# MultiRotorHub.net
KiCad netlist of a schematic drawn in EAGLE
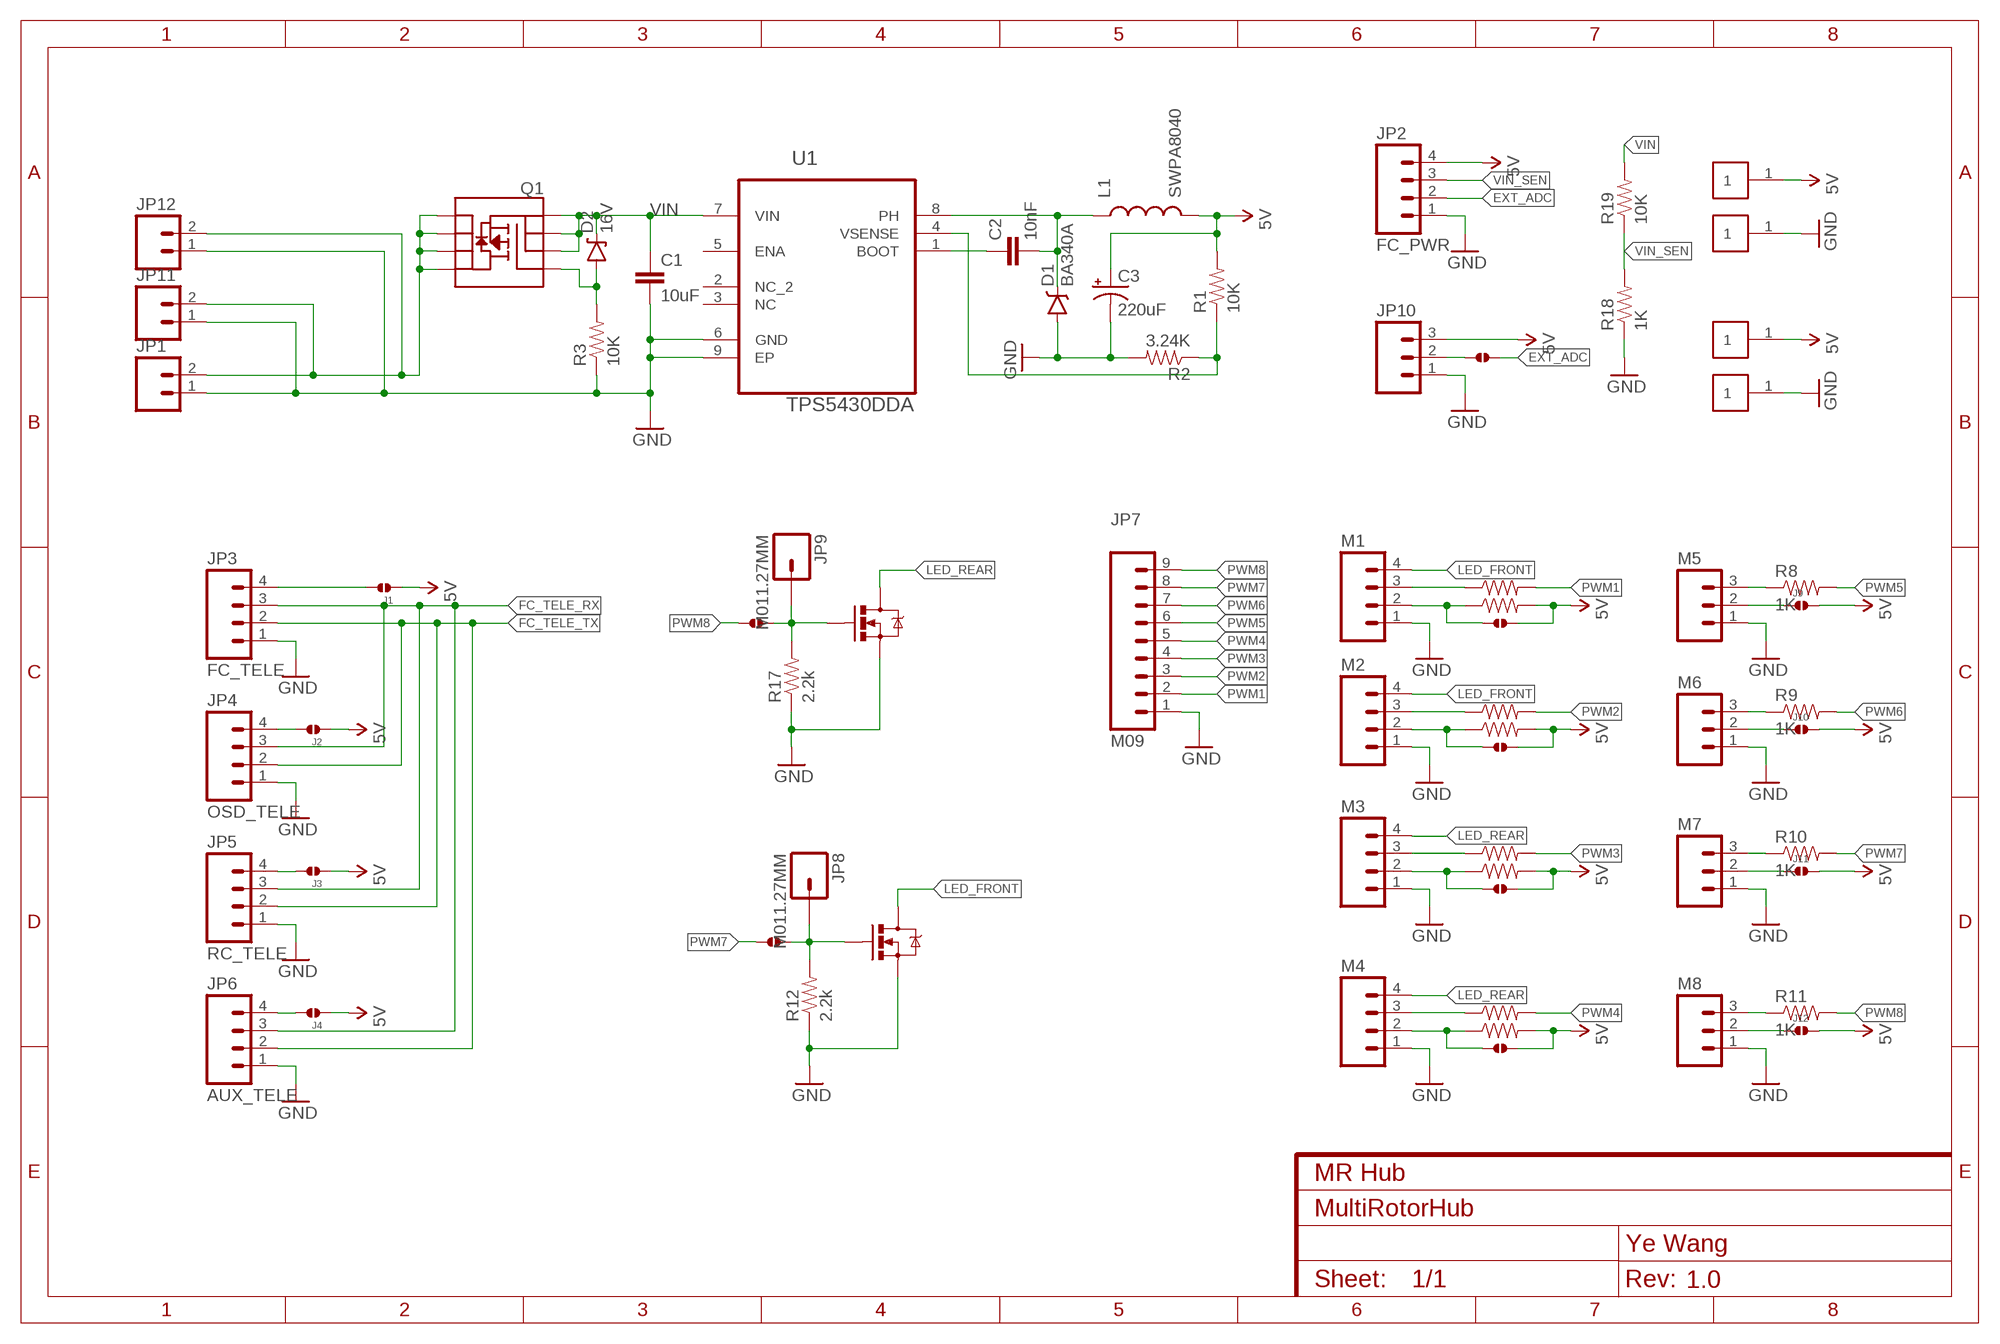
[diagram p0: schematic, sheet 1]

(export (version "E")
  (design (tool "Eeschema 10.0.6"))
  (components
    (comp (ref "C1")
      (value "10uF")
      (footprint "eagle-import:1206")
      (libsource (lib "eagle-import") (part "CAP1206"))
    )
    (comp (ref "C2")
      (value "10nF")
      (footprint "eagle-import:0603-CAP")
      (libsource (lib "eagle-import") (part "10NF/10000PF-50V-10%(0603)"))
    )
    (comp (ref "C3")
      (value "220uF")
      (footprint "eagle-import:PANASONIC_D")
      (libsource (lib "eagle-import") (part "CAP_POLD"))
    )
    (comp (ref "CON1")
      (value "CON1P2.54MM")
      (footprint "eagle-import:SMD2.54MM")
      (libsource (lib "eagle-import") (part "CON1P2.54MM"))
    )
    (comp (ref "CON2")
      (value "CON1P2.54MM")
      (footprint "eagle-import:SMD2.54MM")
      (libsource (lib "eagle-import") (part "CON1P2.54MM"))
    )
    (comp (ref "CON3")
      (value "CON1P2.54MM")
      (footprint "eagle-import:SMD2.54MM")
      (libsource (lib "eagle-import") (part "CON1P2.54MM"))
    )
    (comp (ref "CON4")
      (value "CON1P2.54MM")
      (footprint "eagle-import:SMD2.54MM")
      (libsource (lib "eagle-import") (part "CON1P2.54MM"))
    )
    (comp (ref "D1")
      (value "BA340A")
      (footprint "eagle-import:SMA-DIODE")
      (libsource (lib "eagle-import") (part "B340A"))
    )
    (comp (ref "D2")
      (value "16V")
      (footprint "eagle-import:SOD-123")
      (libsource (lib "eagle-import") (part "DIODE-ZENER16V"))
    )
    (comp (ref "J1")
      (value "SOLDERJUMPER.2.MED")
      (footprint "eagle-import:2.MED")
      (libsource (lib "eagle-import") (part "SOLDERJUMPER.2.MED"))
    )
    (comp (ref "J2")
      (value "SOLDERJUMPER.2.MED")
      (footprint "eagle-import:2.MED")
      (libsource (lib "eagle-import") (part "SOLDERJUMPER.2.MED"))
    )
    (comp (ref "J3")
      (value "SOLDERJUMPER.2.MED")
      (footprint "eagle-import:2.MED")
      (libsource (lib "eagle-import") (part "SOLDERJUMPER.2.MED"))
    )
    (comp (ref "J4")
      (value "SOLDERJUMPER.2.MED")
      (footprint "eagle-import:2.MED")
      (libsource (lib "eagle-import") (part "SOLDERJUMPER.2.MED"))
    )
    (comp (ref "J5")
      (value "SOLDERJUMPER.2.MED")
      (footprint "eagle-import:2.MED")
      (libsource (lib "eagle-import") (part "SOLDERJUMPER.2.MED"))
    )
    (comp (ref "J6")
      (value "SOLDERJUMPER.2.MED")
      (footprint "eagle-import:2.MED")
      (libsource (lib "eagle-import") (part "SOLDERJUMPER.2.MED"))
    )
    (comp (ref "J7")
      (value "SOLDERJUMPER.2.MED")
      (footprint "eagle-import:2.MED")
      (libsource (lib "eagle-import") (part "SOLDERJUMPER.2.MED"))
    )
    (comp (ref "J8")
      (value "SOLDERJUMPER.2.MED")
      (footprint "eagle-import:2.MED")
      (libsource (lib "eagle-import") (part "SOLDERJUMPER.2.MED"))
    )
    (comp (ref "J9")
      (value "SOLDERJUMPER.2.MED")
      (footprint "eagle-import:2.MED")
      (libsource (lib "eagle-import") (part "SOLDERJUMPER.2.MED"))
    )
    (comp (ref "J10")
      (value "SOLDERJUMPER.2.MED")
      (footprint "eagle-import:2.MED")
      (libsource (lib "eagle-import") (part "SOLDERJUMPER.2.MED"))
    )
    (comp (ref "J11")
      (value "SOLDERJUMPER.2.MED")
      (footprint "eagle-import:2.MED")
      (libsource (lib "eagle-import") (part "SOLDERJUMPER.2.MED"))
    )
    (comp (ref "J12")
      (value "SOLDERJUMPER.2.MED")
      (footprint "eagle-import:2.MED")
      (libsource (lib "eagle-import") (part "SOLDERJUMPER.2.MED"))
    )
    (comp (ref "J13")
      (value "SOLDERJUMPER.2.MED")
      (footprint "eagle-import:2.MED")
      (libsource (lib "eagle-import") (part "SOLDERJUMPER.2.MED"))
    )
    (comp (ref "J14")
      (value "SOLDERJUMPER.2.MED")
      (footprint "eagle-import:2.MED")
      (libsource (lib "eagle-import") (part "SOLDERJUMPER.2.MED"))
    )
    (comp (ref "J15")
      (value "SOLDERJUMPER.2.MED")
      (footprint "eagle-import:2.MED")
      (libsource (lib "eagle-import") (part "SOLDERJUMPER.2.MED"))
    )
    (comp (ref "JP1")
      (value "M02PTH")
      (footprint "eagle-import:1X02")
      (libsource (lib "eagle-import") (part "M02PTH"))
    )
    (comp (ref "JP2")
      (value "FC_PWR")
      (footprint "eagle-import:1X04-1.27MM")
      (libsource (lib "eagle-import") (part "M041.27MM"))
    )
    (comp (ref "JP3")
      (value "FC_TELE")
      (footprint "eagle-import:1X04-1.27MM")
      (libsource (lib "eagle-import") (part "M041.27MM"))
    )
    (comp (ref "JP4")
      (value "OSD_TELE")
      (footprint "eagle-import:1X04-1.27MM")
      (libsource (lib "eagle-import") (part "M041.27MM"))
    )
    (comp (ref "JP5")
      (value "RC_TELE")
      (footprint "eagle-import:1X04-1.27MM")
      (libsource (lib "eagle-import") (part "M041.27MM"))
    )
    (comp (ref "JP6")
      (value "AUX_TELE")
      (footprint "eagle-import:1X04-1.27MM")
      (libsource (lib "eagle-import") (part "M041.27MM"))
    )
    (comp (ref "JP7")
      (value "M09")
      (footprint "eagle-import:1X09")
      (libsource (lib "eagle-import") (part "M09"))
    )
    (comp (ref "JP8")
      (value "M011.27MM")
      (footprint "eagle-import:1X01-1.27MM")
      (libsource (lib "eagle-import") (part "M011.27MM"))
    )
    (comp (ref "JP9")
      (value "M011.27MM")
      (footprint "eagle-import:1X01-1.27MM")
      (libsource (lib "eagle-import") (part "M011.27MM"))
    )
    (comp (ref "JP10")
      (value "M03M03-1.27MM")
      (footprint "eagle-import:1X03-1.27MM")
      (libsource (lib "eagle-import") (part "M03M03-1.27MM"))
    )
    (comp (ref "JP11")
      (value "M02PTH")
      (footprint "eagle-import:1X02")
      (libsource (lib "eagle-import") (part "M02PTH"))
    )
    (comp (ref "JP12")
      (value "M02PTH")
      (footprint "eagle-import:1X02")
      (libsource (lib "eagle-import") (part "M02PTH"))
    )
    (comp (ref "L1")
      (value "SWPA8040")
      (footprint "eagle-import:INC8040")
      (libsource (lib "eagle-import") (part "SWPA8040"))
    )
    (comp (ref "M1")
      (value "M04PTH")
      (footprint "eagle-import:1X04")
      (libsource (lib "eagle-import") (part "M04PTH"))
    )
    (comp (ref "M2")
      (value "M04PTH")
      (footprint "eagle-import:1X04")
      (libsource (lib "eagle-import") (part "M04PTH"))
    )
    (comp (ref "M3")
      (value "M04PTH")
      (footprint "eagle-import:1X04")
      (libsource (lib "eagle-import") (part "M04PTH"))
    )
    (comp (ref "M4")
      (value "M04PTH")
      (footprint "eagle-import:1X04")
      (libsource (lib "eagle-import") (part "M04PTH"))
    )
    (comp (ref "M5")
      (value "M03PTH")
      (footprint "eagle-import:1X03")
      (libsource (lib "eagle-import") (part "M03PTH"))
    )
    (comp (ref "M6")
      (value "M03PTH")
      (footprint "eagle-import:1X03")
      (libsource (lib "eagle-import") (part "M03PTH"))
    )
    (comp (ref "M7")
      (value "M03PTH")
      (footprint "eagle-import:1X03")
      (libsource (lib "eagle-import") (part "M03PTH"))
    )
    (comp (ref "M8")
      (value "M03PTH")
      (footprint "eagle-import:1X03")
      (libsource (lib "eagle-import") (part "M03PTH"))
    )
    (comp (ref "Q1")
      (value "MOSFET-PCHANNEL-SOIC8SOIC8")
      (footprint "eagle-import:SO08")
      (libsource (lib "eagle-import") (part "MOSFET-PCHANNEL-SOIC8SOIC8"))
    )
    (comp (ref "Q2")
      (value "MOSFET-NCHANNELBSS123LT1G")
      (footprint "eagle-import:SOT23-3")
      (libsource (lib "eagle-import") (part "MOSFET-NCHANNELBSS123LT1G"))
    )
    (comp (ref "Q3")
      (value "MOSFET-NCHANNELBSS123LT1G")
      (footprint "eagle-import:SOT23-3")
      (libsource (lib "eagle-import") (part "MOSFET-NCHANNELBSS123LT1G"))
    )
    (comp (ref "R1")
      (value "10K")
      (footprint "eagle-import:0603-RES")
      (libsource (lib "eagle-import") (part "10KOHM-1/10W-1%(0603)0603"))
    )
    (comp (ref "R2")
      (value "3.24K")
      (footprint "eagle-import:0603-RES")
      (libsource (lib "eagle-import") (part "RESISTOR0603-RES"))
    )
    (comp (ref "R3")
      (value "10K")
      (footprint "eagle-import:0603-RES")
      (libsource (lib "eagle-import") (part "10KOHM-1/10W-1%(0603)0603"))
    )
    (comp (ref "R4")
      (value "1K")
      (footprint "eagle-import:0603-RES")
      (libsource (lib "eagle-import") (part "RESISTOR0603-RES"))
    )
    (comp (ref "R5")
      (value "1K")
      (footprint "eagle-import:0603-RES")
      (libsource (lib "eagle-import") (part "RESISTOR0603-RES"))
    )
    (comp (ref "R6")
      (value "1K")
      (footprint "eagle-import:0603-RES")
      (libsource (lib "eagle-import") (part "RESISTOR0603-RES"))
    )
    (comp (ref "R7")
      (value "1K")
      (footprint "eagle-import:0603-RES")
      (libsource (lib "eagle-import") (part "RESISTOR0603-RES"))
    )
    (comp (ref "R8")
      (value "1K")
      (footprint "eagle-import:0603-RES")
      (libsource (lib "eagle-import") (part "RESISTOR0603-RES"))
    )
    (comp (ref "R9")
      (value "1K")
      (footprint "eagle-import:0603-RES")
      (libsource (lib "eagle-import") (part "RESISTOR0603-RES"))
    )
    (comp (ref "R10")
      (value "1K")
      (footprint "eagle-import:0603-RES")
      (libsource (lib "eagle-import") (part "RESISTOR0603-RES"))
    )
    (comp (ref "R11")
      (value "1K")
      (footprint "eagle-import:0603-RES")
      (libsource (lib "eagle-import") (part "RESISTOR0603-RES"))
    )
    (comp (ref "R12")
      (value "2.2k")
      (footprint "eagle-import:0603-RES")
      (libsource (lib "eagle-import") (part "2.2KOHM-1/10W-1%(0603)"))
    )
    (comp (ref "R13")
      (value "10")
      (footprint "eagle-import:R2512")
      (libsource (lib "eagle-import") (part "RESISTOR2512"))
    )
    (comp (ref "R14")
      (value "10")
      (footprint "eagle-import:R2512")
      (libsource (lib "eagle-import") (part "RESISTOR2512"))
    )
    (comp (ref "R15")
      (value "10")
      (footprint "eagle-import:R2512")
      (libsource (lib "eagle-import") (part "RESISTOR2512"))
    )
    (comp (ref "R16")
      (value "10")
      (footprint "eagle-import:R2512")
      (libsource (lib "eagle-import") (part "RESISTOR2512"))
    )
    (comp (ref "R17")
      (value "2.2k")
      (footprint "eagle-import:0603-RES")
      (libsource (lib "eagle-import") (part "2.2KOHM-1/10W-1%(0603)"))
    )
    (comp (ref "R18")
      (value "1K")
      (footprint "eagle-import:0603-RES")
      (libsource (lib "eagle-import") (part "1KOHM-1/10W-1%(0603)"))
    )
    (comp (ref "R19")
      (value "10K")
      (footprint "eagle-import:0603-RES")
      (libsource (lib "eagle-import") (part "10KOHM-1/10W-1%(0603)0603"))
    )
    (comp (ref "U1")
      (value "TPS5430DDA")
      (footprint "eagle-import:SOIC127P600X170-9N")
      (libsource (lib "eagle-import") (part "TPS5430DDA"))
    )
  )
  (nets
    (net (code "1") (name "5V") (class "Default")
      (node (ref "C3") (pin "+") (pinfunction "+_+") (pintype "passive"))
      (node (ref "CON1") (pin "1") (pinfunction "1_1") (pintype "bidirectional"))
      (node (ref "CON3") (pin "1") (pinfunction "1_1") (pintype "bidirectional"))
      (node (ref "J1") (pin "1") (pinfunction "1_1") (pintype "bidirectional"))
      (node (ref "J10") (pin "2") (pinfunction "2_2") (pintype "bidirectional"))
      (node (ref "J11") (pin "2") (pinfunction "2_2") (pintype "bidirectional"))
      (node (ref "J12") (pin "2") (pinfunction "2_2") (pintype "bidirectional"))
      (node (ref "J2") (pin "1") (pinfunction "1_1") (pintype "bidirectional"))
      (node (ref "J3") (pin "1") (pinfunction "1_1") (pintype "bidirectional"))
      (node (ref "J4") (pin "1") (pinfunction "1_1") (pintype "bidirectional"))
      (node (ref "J5") (pin "2") (pinfunction "2_2") (pintype "bidirectional"))
      (node (ref "J6") (pin "2") (pinfunction "2_2") (pintype "bidirectional"))
      (node (ref "J7") (pin "2") (pinfunction "2_2") (pintype "bidirectional"))
      (node (ref "J8") (pin "2") (pinfunction "2_2") (pintype "bidirectional"))
      (node (ref "J9") (pin "2") (pinfunction "2_2") (pintype "bidirectional"))
      (node (ref "JP10") (pin "3") (pinfunction "3_3") (pintype "passive"))
      (node (ref "JP2") (pin "4") (pinfunction "4_4") (pintype "passive"))
      (node (ref "L1") (pin "2") (pinfunction "2_2") (pintype "passive"))
      (node (ref "R1") (pin "2") (pinfunction "2_2") (pintype "passive"))
      (node (ref "R13") (pin "2") (pinfunction "2_2") (pintype "passive"))
      (node (ref "R14") (pin "2") (pinfunction "2_2") (pintype "passive"))
      (node (ref "R15") (pin "2") (pinfunction "2_2") (pintype "passive"))
      (node (ref "R16") (pin "2") (pinfunction "2_2") (pintype "passive"))
    )
    (net (code "2") (name "EXT_ADC") (class "Default")
      (node (ref "J15") (pin "2") (pinfunction "2_2") (pintype "bidirectional"))
      (node (ref "JP2") (pin "2") (pinfunction "2_2") (pintype "passive"))
    )
    (net (code "3") (name "FC_TELE_RX") (class "Default")
      (node (ref "JP3") (pin "3") (pinfunction "3_3") (pintype "passive"))
      (node (ref "JP4") (pin "3") (pinfunction "3_3") (pintype "passive"))
      (node (ref "JP5") (pin "3") (pinfunction "3_3") (pintype "passive"))
      (node (ref "JP6") (pin "3") (pinfunction "3_3") (pintype "passive"))
    )
    (net (code "4") (name "FC_TELE_TX") (class "Default")
      (node (ref "JP3") (pin "2") (pinfunction "2_2") (pintype "passive"))
      (node (ref "JP4") (pin "2") (pinfunction "2_2") (pintype "passive"))
      (node (ref "JP5") (pin "2") (pinfunction "2_2") (pintype "passive"))
      (node (ref "JP6") (pin "2") (pinfunction "2_2") (pintype "passive"))
    )
    (net (code "5") (name "GND") (class "Default")
      (node (ref "C1") (pin "2") (pinfunction "2_2") (pintype "passive"))
      (node (ref "C3") (pin "-") (pinfunction "-_-") (pintype "passive"))
      (node (ref "CON2") (pin "1") (pinfunction "1_1") (pintype "bidirectional"))
      (node (ref "CON4") (pin "1") (pinfunction "1_1") (pintype "bidirectional"))
      (node (ref "D1") (pin "A") (pinfunction "A_A") (pintype "passive"))
      (node (ref "JP1") (pin "1") (pinfunction "1_1") (pintype "passive"))
      (node (ref "JP10") (pin "1") (pinfunction "1_1") (pintype "passive"))
      (node (ref "JP11") (pin "1") (pinfunction "1_1") (pintype "passive"))
      (node (ref "JP12") (pin "1") (pinfunction "1_1") (pintype "passive"))
      (node (ref "JP2") (pin "1") (pinfunction "1_1") (pintype "passive"))
      (node (ref "JP3") (pin "1") (pinfunction "1_1") (pintype "passive"))
      (node (ref "JP4") (pin "1") (pinfunction "1_1") (pintype "passive"))
      (node (ref "JP5") (pin "1") (pinfunction "1_1") (pintype "passive"))
      (node (ref "JP6") (pin "1") (pinfunction "1_1") (pintype "passive"))
      (node (ref "JP7") (pin "1") (pinfunction "1_1") (pintype "passive"))
      (node (ref "M1") (pin "1") (pinfunction "1_1") (pintype "passive"))
      (node (ref "M2") (pin "1") (pinfunction "1_1") (pintype "passive"))
      (node (ref "M3") (pin "1") (pinfunction "1_1") (pintype "passive"))
      (node (ref "M4") (pin "1") (pinfunction "1_1") (pintype "passive"))
      (node (ref "M5") (pin "1") (pinfunction "1_1") (pintype "passive"))
      (node (ref "M6") (pin "1") (pinfunction "1_1") (pintype "passive"))
      (node (ref "M7") (pin "1") (pinfunction "1_1") (pintype "passive"))
      (node (ref "M8") (pin "1") (pinfunction "1_1") (pintype "passive"))
      (node (ref "Q2") (pin "2") (pinfunction "S_2") (pintype "passive"))
      (node (ref "Q3") (pin "2") (pinfunction "S_2") (pintype "passive"))
      (node (ref "R12") (pin "1") (pinfunction "1_1") (pintype "passive"))
      (node (ref "R17") (pin "1") (pinfunction "1_1") (pintype "passive"))
      (node (ref "R18") (pin "1") (pinfunction "1_1") (pintype "passive"))
      (node (ref "R2") (pin "2") (pinfunction "2_2") (pintype "passive"))
      (node (ref "R3") (pin "1") (pinfunction "1_1") (pintype "passive"))
      (node (ref "U1") (pin "6") (pinfunction "GND_6") (pintype "passive"))
      (node (ref "U1") (pin "9") (pinfunction "EP_9") (pintype "passive"))
    )
    (net (code "6") (name "LED_FRONT") (class "Default")
      (node (ref "M1") (pin "4") (pinfunction "4_4") (pintype "passive"))
      (node (ref "M2") (pin "4") (pinfunction "4_4") (pintype "passive"))
      (node (ref "Q2") (pin "3") (pinfunction "D_3") (pintype "passive"))
    )
    (net (code "7") (name "LED_REAR") (class "Default")
      (node (ref "M3") (pin "4") (pinfunction "4_4") (pintype "passive"))
      (node (ref "M4") (pin "4") (pinfunction "4_4") (pintype "passive"))
      (node (ref "Q3") (pin "3") (pinfunction "D_3") (pintype "passive"))
    )
    (net (code "8") (name "Net-(J1-Pad2)") (class "Default")
      (node (ref "J1") (pin "2") (pinfunction "2_2") (pintype "bidirectional"))
      (node (ref "JP3") (pin "4") (pinfunction "4_4") (pintype "passive"))
    )
    (net (code "9") (name "Net-(J2-Pad2)") (class "Default")
      (node (ref "J2") (pin "2") (pinfunction "2_2") (pintype "bidirectional"))
      (node (ref "JP4") (pin "4") (pinfunction "4_4") (pintype "passive"))
    )
    (net (code "10") (name "Net-(J3-Pad2)") (class "Default")
      (node (ref "J3") (pin "2") (pinfunction "2_2") (pintype "bidirectional"))
      (node (ref "JP5") (pin "4") (pinfunction "4_4") (pintype "passive"))
    )
    (net (code "11") (name "Net-(J4-Pad2)") (class "Default")
      (node (ref "J4") (pin "2") (pinfunction "2_2") (pintype "bidirectional"))
      (node (ref "JP6") (pin "4") (pinfunction "4_4") (pintype "passive"))
    )
    (net (code "12") (name "Net-(J5-Pad1)") (class "Default")
      (node (ref "J5") (pin "1") (pinfunction "1_1") (pintype "bidirectional"))
      (node (ref "M1") (pin "2") (pinfunction "2_2") (pintype "passive"))
      (node (ref "R13") (pin "1") (pinfunction "1_1") (pintype "passive"))
    )
    (net (code "13") (name "Net-(J6-Pad1)") (class "Default")
      (node (ref "J6") (pin "1") (pinfunction "1_1") (pintype "bidirectional"))
      (node (ref "M2") (pin "2") (pinfunction "2_2") (pintype "passive"))
      (node (ref "R14") (pin "1") (pinfunction "1_1") (pintype "passive"))
    )
    (net (code "14") (name "Net-(J7-Pad1)") (class "Default")
      (node (ref "J7") (pin "1") (pinfunction "1_1") (pintype "bidirectional"))
      (node (ref "M3") (pin "2") (pinfunction "2_2") (pintype "passive"))
      (node (ref "R15") (pin "1") (pinfunction "1_1") (pintype "passive"))
    )
    (net (code "15") (name "Net-(J8-Pad1)") (class "Default")
      (node (ref "J8") (pin "1") (pinfunction "1_1") (pintype "bidirectional"))
      (node (ref "M4") (pin "2") (pinfunction "2_2") (pintype "passive"))
      (node (ref "R16") (pin "1") (pinfunction "1_1") (pintype "passive"))
    )
    (net (code "16") (name "Net-(J9-Pad1)") (class "Default")
      (node (ref "J9") (pin "1") (pinfunction "1_1") (pintype "bidirectional"))
      (node (ref "M5") (pin "2") (pinfunction "2_2") (pintype "passive"))
    )
    (net (code "17") (name "Net-(J10-Pad1)") (class "Default")
      (node (ref "J10") (pin "1") (pinfunction "1_1") (pintype "bidirectional"))
      (node (ref "M6") (pin "2") (pinfunction "2_2") (pintype "passive"))
    )
    (net (code "18") (name "Net-(J11-Pad1)") (class "Default")
      (node (ref "J11") (pin "1") (pinfunction "1_1") (pintype "bidirectional"))
      (node (ref "M7") (pin "2") (pinfunction "2_2") (pintype "passive"))
    )
    (net (code "19") (name "Net-(J12-Pad1)") (class "Default")
      (node (ref "J12") (pin "1") (pinfunction "1_1") (pintype "bidirectional"))
      (node (ref "M8") (pin "2") (pinfunction "2_2") (pintype "passive"))
    )
    (net (code "20") (name "Net-(J15-Pad1)") (class "Default")
      (node (ref "J15") (pin "1") (pinfunction "1_1") (pintype "bidirectional"))
      (node (ref "JP10") (pin "2") (pinfunction "2_2") (pintype "passive"))
    )
    (net (code "21") (name "Net-(JP1-Pad2)") (class "Default")
      (node (ref "JP1") (pin "2") (pinfunction "2_2") (pintype "passive"))
      (node (ref "JP11") (pin "2") (pinfunction "2_2") (pintype "passive"))
      (node (ref "JP12") (pin "2") (pinfunction "2_2") (pintype "passive"))
      (node (ref "Q1") (pin "5") (pinfunction "D_5") (pintype "bidirectional"))
      (node (ref "Q1") (pin "6") (pinfunction "D_6") (pintype "bidirectional"))
      (node (ref "Q1") (pin "7") (pinfunction "D_7") (pintype "bidirectional"))
      (node (ref "Q1") (pin "8") (pinfunction "D_8") (pintype "bidirectional"))
    )
    (net (code "22") (name "Net-(M1-Pad3)") (class "Default")
      (node (ref "M1") (pin "3") (pinfunction "3_3") (pintype "passive"))
      (node (ref "R4") (pin "1") (pinfunction "1_1") (pintype "passive"))
    )
    (net (code "23") (name "Net-(M2-Pad3)") (class "Default")
      (node (ref "M2") (pin "3") (pinfunction "3_3") (pintype "passive"))
      (node (ref "R5") (pin "1") (pinfunction "1_1") (pintype "passive"))
    )
    (net (code "24") (name "Net-(M3-Pad3)") (class "Default")
      (node (ref "M3") (pin "3") (pinfunction "3_3") (pintype "passive"))
      (node (ref "R6") (pin "1") (pinfunction "1_1") (pintype "passive"))
    )
    (net (code "25") (name "Net-(M4-Pad3)") (class "Default")
      (node (ref "M4") (pin "3") (pinfunction "3_3") (pintype "passive"))
      (node (ref "R7") (pin "1") (pinfunction "1_1") (pintype "passive"))
    )
    (net (code "26") (name "Net-(M5-Pad3)") (class "Default")
      (node (ref "M5") (pin "3") (pinfunction "3_3") (pintype "passive"))
      (node (ref "R8") (pin "1") (pinfunction "1_1") (pintype "passive"))
    )
    (net (code "27") (name "Net-(M6-Pad3)") (class "Default")
      (node (ref "M6") (pin "3") (pinfunction "3_3") (pintype "passive"))
      (node (ref "R9") (pin "1") (pinfunction "1_1") (pintype "passive"))
    )
    (net (code "28") (name "Net-(M7-Pad3)") (class "Default")
      (node (ref "M7") (pin "3") (pinfunction "3_3") (pintype "passive"))
      (node (ref "R10") (pin "1") (pinfunction "1_1") (pintype "passive"))
    )
    (net (code "29") (name "Net-(M8-Pad3)") (class "Default")
      (node (ref "M8") (pin "3") (pinfunction "3_3") (pintype "passive"))
      (node (ref "R11") (pin "1") (pinfunction "1_1") (pintype "passive"))
    )
    (net (code "30") (name "Net-(Q1-G)") (class "Default")
      (node (ref "D2") (pin "A") (pinfunction "A_A") (pintype "passive"))
      (node (ref "Q1") (pin "4") (pinfunction "G_4") (pintype "bidirectional"))
      (node (ref "R3") (pin "2") (pinfunction "2_2") (pintype "passive"))
    )
    (net (code "31") (name "Net-(Q2-G)") (class "Default")
      (node (ref "J13") (pin "2") (pinfunction "2_2") (pintype "bidirectional"))
      (node (ref "JP8") (pin "1") (pinfunction "1_1") (pintype "passive"))
      (node (ref "Q2") (pin "1") (pinfunction "G_1") (pintype "passive"))
      (node (ref "R12") (pin "2") (pinfunction "2_2") (pintype "passive"))
    )
    (net (code "32") (name "Net-(Q3-G)") (class "Default")
      (node (ref "J14") (pin "2") (pinfunction "2_2") (pintype "bidirectional"))
      (node (ref "JP9") (pin "1") (pinfunction "1_1") (pintype "passive"))
      (node (ref "Q3") (pin "1") (pinfunction "G_1") (pintype "passive"))
      (node (ref "R17") (pin "2") (pinfunction "2_2") (pintype "passive"))
    )
    (net (code "33") (name "Net-(U1-BOOT)") (class "Default")
      (node (ref "C2") (pin "1") (pinfunction "1_1") (pintype "passive"))
      (node (ref "U1") (pin "1") (pinfunction "BOOT_1") (pintype "passive"))
    )
    (net (code "34") (name "Net-(U1-PH)") (class "Default")
      (node (ref "C2") (pin "2") (pinfunction "2_2") (pintype "passive"))
      (node (ref "D1") (pin "C") (pinfunction "C_C") (pintype "passive"))
      (node (ref "L1") (pin "1") (pinfunction "1_1") (pintype "passive"))
      (node (ref "U1") (pin "8") (pinfunction "PH_8") (pintype "output"))
    )
    (net (code "35") (name "Net-(U1-VSENSE)") (class "Default")
      (node (ref "R1") (pin "1") (pinfunction "1_1") (pintype "passive"))
      (node (ref "R2") (pin "1") (pinfunction "1_1") (pintype "passive"))
      (node (ref "U1") (pin "4") (pinfunction "VSENSE_4") (pintype "output"))
    )
    (net (code "36") (name "PWM1") (class "Default")
      (node (ref "JP7") (pin "2") (pinfunction "2_2") (pintype "passive"))
      (node (ref "R4") (pin "2") (pinfunction "2_2") (pintype "passive"))
    )
    (net (code "37") (name "PWM2") (class "Default")
      (node (ref "JP7") (pin "3") (pinfunction "3_3") (pintype "passive"))
      (node (ref "R5") (pin "2") (pinfunction "2_2") (pintype "passive"))
    )
    (net (code "38") (name "PWM3") (class "Default")
      (node (ref "JP7") (pin "4") (pinfunction "4_4") (pintype "passive"))
      (node (ref "R6") (pin "2") (pinfunction "2_2") (pintype "passive"))
    )
    (net (code "39") (name "PWM4") (class "Default")
      (node (ref "JP7") (pin "5") (pinfunction "5_5") (pintype "passive"))
      (node (ref "R7") (pin "2") (pinfunction "2_2") (pintype "passive"))
    )
    (net (code "40") (name "PWM5") (class "Default")
      (node (ref "JP7") (pin "6") (pinfunction "6_6") (pintype "passive"))
      (node (ref "R8") (pin "2") (pinfunction "2_2") (pintype "passive"))
    )
    (net (code "41") (name "PWM6") (class "Default")
      (node (ref "JP7") (pin "7") (pinfunction "7_7") (pintype "passive"))
      (node (ref "R9") (pin "2") (pinfunction "2_2") (pintype "passive"))
    )
    (net (code "42") (name "PWM7") (class "Default")
      (node (ref "J13") (pin "1") (pinfunction "1_1") (pintype "bidirectional"))
      (node (ref "JP7") (pin "8") (pinfunction "8_8") (pintype "passive"))
      (node (ref "R10") (pin "2") (pinfunction "2_2") (pintype "passive"))
    )
    (net (code "43") (name "PWM8") (class "Default")
      (node (ref "J14") (pin "1") (pinfunction "1_1") (pintype "bidirectional"))
      (node (ref "JP7") (pin "9") (pinfunction "9_9") (pintype "passive"))
      (node (ref "R11") (pin "2") (pinfunction "2_2") (pintype "passive"))
    )
    (net (code "44") (name "VIN") (class "Default")
      (node (ref "C1") (pin "1") (pinfunction "1_1") (pintype "passive"))
      (node (ref "D2") (pin "C") (pinfunction "C_C") (pintype "passive"))
      (node (ref "Q1") (pin "1") (pinfunction "S_1") (pintype "bidirectional"))
      (node (ref "Q1") (pin "2") (pinfunction "S_2") (pintype "bidirectional"))
      (node (ref "Q1") (pin "3") (pinfunction "S_3") (pintype "bidirectional"))
      (node (ref "R19") (pin "2") (pinfunction "2_2") (pintype "passive"))
      (node (ref "U1") (pin "7") (pinfunction "VIN_7") (pintype "input"))
    )
    (net (code "45") (name "VIN_SEN") (class "Default")
      (node (ref "JP2") (pin "3") (pinfunction "3_3") (pintype "passive"))
      (node (ref "R18") (pin "2") (pinfunction "2_2") (pintype "passive"))
      (node (ref "R19") (pin "1") (pinfunction "1_1") (pintype "passive"))
    )
    (net (code "46") (name "unconnected-(U1-ENA-Pad5)") (class "Default")
      (node (ref "U1") (pin "5") (pinfunction "ENA_5") (pintype "input"))
    )
    (net (code "47") (name "unconnected-(U1-NC-Pad3)") (class "Default")
      (node (ref "U1") (pin "3") (pinfunction "NC_3") (pintype "no_connect"))
    )
    (net (code "48") (name "unconnected-(U1-NC_2-Pad2)") (class "Default")
      (node (ref "U1") (pin "2") (pinfunction "NC_2_2") (pintype "no_connect"))
    )
  )
)
